# Inverter_Power.net
KiCad netlist of a schematic drawn in Altium Designer
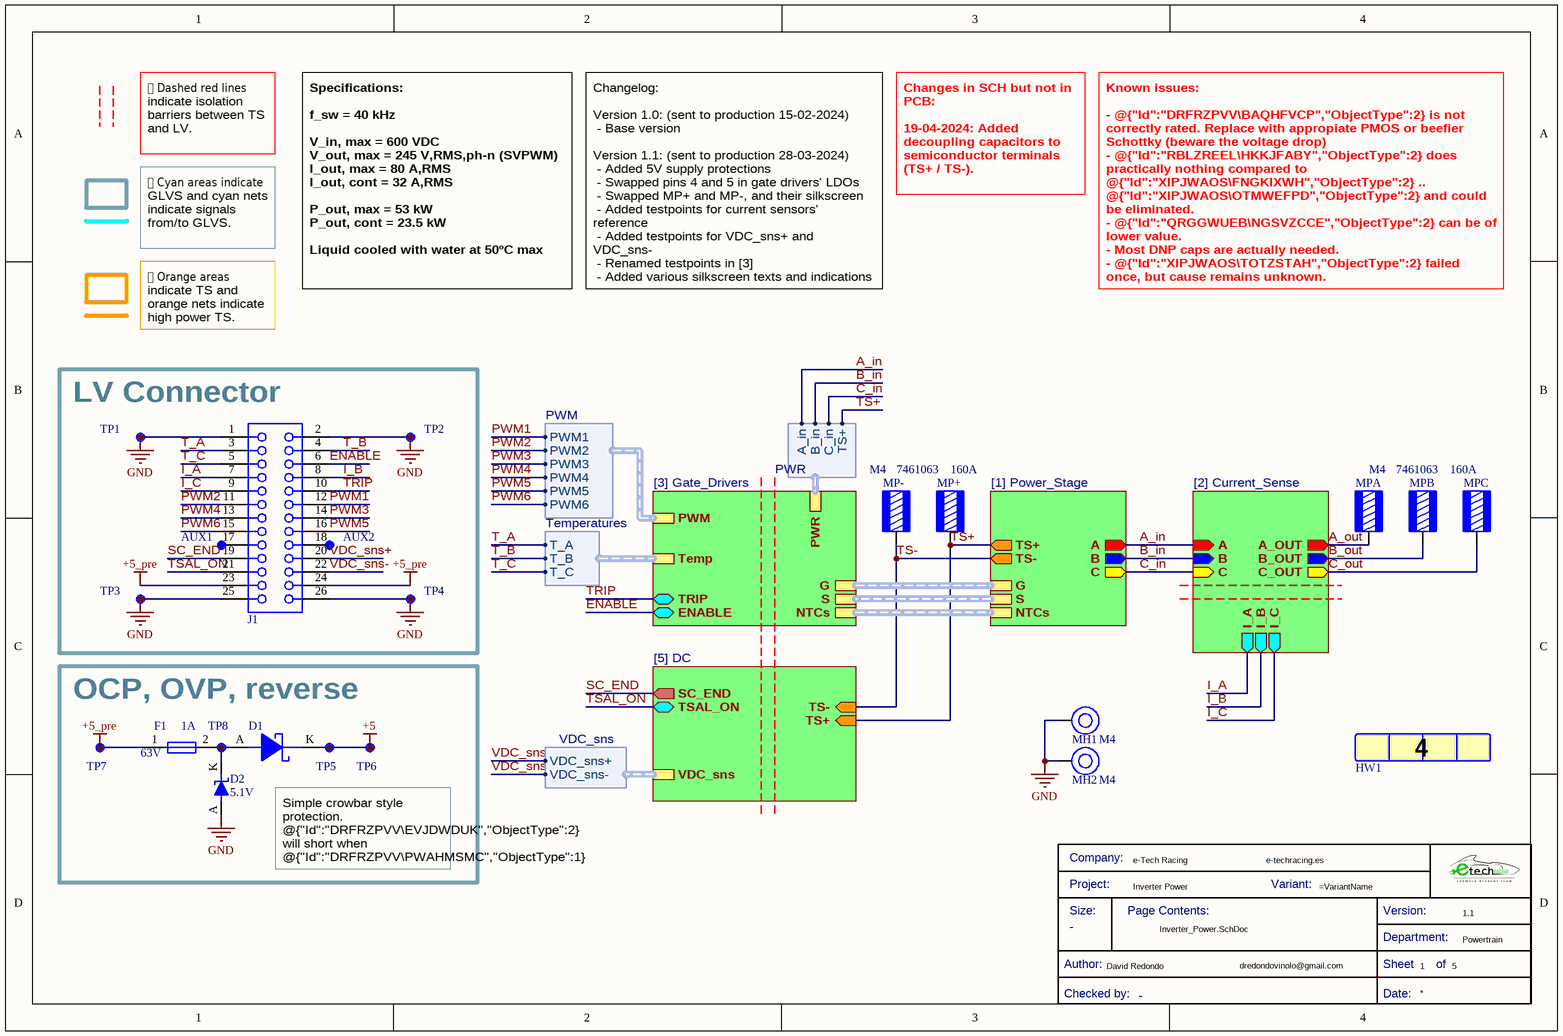
[diagram p0: Inverter_Power.SchDoc]

(export (version "E")
  (design (tool "Eeschema 10.0.6"))
  (components
    (comp (ref "*")
      (value "Title Block_template")
      (description "Standard Title Block")
      (fields
        (field (name "SIZE") "-")
        (field (name ".CREATOR") "GP")
        (field (name ".PCBCHECK") "GP")
        (field (name ".SCHCHECK") "GP")
      )
      (libsource (lib "e-Tech_Racing") (part "Title Block_template"))
    )
    (comp (ref "AUX1")
      (value "TestPoint")
      (footprint "TestPoint")
      (description "Test Point 1x1 mm")
      (fields (field (name ".CREATOR") "GP") (field (name ".PCBCHECK") "GP") (field (name ".SCHCHECK") "GP"))
      (libsource (lib "Inverter_Libraries") (part "TestPoint"))
    )
    (comp (ref "AUX2")
      (value "TestPoint")
      (footprint "TestPoint")
      (description "Test Point 1x1 mm")
      (fields (field (name ".CREATOR") "GP") (field (name ".PCBCHECK") "GP") (field (name ".SCHCHECK") "GP"))
      (libsource (lib "Inverter_Libraries") (part "TestPoint"))
    )
    (comp (ref "D1")
      (value "MBR0530")
      (footprint "DSC-SOD123")
      (description "VR=30V IF=500mA 30pF P=410mW")
      (fields (field (name ".CREATOR") "GP"))
      (libsource (lib "Filter components") (part "DSC-0.5/30-SOD123"))
    )
    (comp (ref "D2")
      (value "BZG05C5V1-E3-TR")
      (footprint "DZ-6.2V-DO-214AC")
      (description "Zener Diode, 5.1V V(Z), 5.88%, 1.25W, Silicon, Unidirectional, DO-214AC")
      (fields
        (field (name "MANUFACTURER") "Vishay")
        (field (name "MANUFACTURER PART NUMBER") "BZG05C5V1-M3-08")
        (field (name "REFERENCE VOLTAGE-NOM") "5.1V")
      )
      (libsource (lib "Inverter_Libraries") (part "DZ-5.1V-DO-214AC"))
    )
    (comp (ref "F1")
      (value "0437001.WRA")
      (footprint "Fuse_1206")
      (description "Fuse Chip Fast Acting 1A 63V SMD Solder Pad 1206 Ceramic T/R Automotive")
      (fields
        (field (name "MANUFACTURER") "Littelfuse")
        (field (name "CURRENT RATING") "1A")
        (field (name "VOLTAGE RATING (DC)") "63V")
        (field (name ".CREATOR") "DO")
      )
      (libsource (lib "Filter components") (part "Fuse_1A_63V_1206"))
    )
    (comp (ref "HW1")
      (value "LOGO CAPAS (4)")
      (footprint "LOGO_LAYERS_4")
      (description "Logo 4 capas")
      (fields (field (name "AUTHOR") "Enric") (field (name "CHECKED") "False"))
      (libsource (lib "Inverter_Libraries") (part "LOGO CAPAS"))
    )
    (comp (ref "J1")
      (value "613026243121")
      (footprint "613026243121")
      (description "WR-PHD Socket Header, THT, Angled, pitch 2.54mm, 2 Row, 26P")
      (fields (field (name "MANUFACTURER") "Wurth Elektronik"))
      (libsource (lib "Inverter_Libraries") (part "613026243121"))
    )
    (comp (ref "MH1")
      (value "Mounting_Hole_M4")
      (footprint "Mounting_Hole_M4")
      (libsource (lib "Electromechanical") (part "Mounting_Hole_M4"))
    )
    (comp (ref "MH2")
      (value "Mounting_Hole_M4")
      (footprint "Mounting_Hole_M4")
      (libsource (lib "Electromechanical") (part "Mounting_Hole_M4"))
    )
    (comp (ref "MP+")
      (value "M4")
      (footprint "7461063_HAL")
      (description "WP-RATR REDCUBE PRESS-FIT right angled, two-rows, L9W9H14mm, M4, 160A")
      (fields
        (field (name "MANUFACTURER PART NUMBER") "7461063")
        (field (name "MANUFACTURER") "Wurth Elektronik")
      )
      (libsource (lib "Inverter_Libraries") (part "7461063"))
    )
    (comp (ref "MP-")
      (value "M4")
      (footprint "7461063_HAL")
      (description "WP-RATR REDCUBE PRESS-FIT right angled, two-rows, L9W9H14mm, M4, 160A")
      (fields
        (field (name "MANUFACTURER PART NUMBER") "7461063")
        (field (name "MANUFACTURER") "Wurth Elektronik")
        (field (name "RATED CURRENT") "160A")
        (field (name "THREAD SIZE") "M4")
      )
      (libsource (lib "Inverter_Libraries") (part "7461063"))
    )
    (comp (ref "MPA")
      (value "M4")
      (footprint "7461063_HAL")
      (description "WP-RATR REDCUBE PRESS-FIT right angled, two-rows, L9W9H14mm, M4, 160A")
      (fields
        (field (name "MANUFACTURER PART NUMBER") "7461063")
        (field (name "MANUFACTURER") "Wurth Elektronik")
      )
      (libsource (lib "Inverter_Libraries") (part "7461063"))
    )
    (comp (ref "MPB")
      (value "M4")
      (footprint "7461063_HAL")
      (description "WP-RATR REDCUBE PRESS-FIT right angled, two-rows, L9W9H14mm, M4, 160A")
      (fields
        (field (name "MANUFACTURER PART NUMBER") "7461063")
        (field (name "MANUFACTURER") "Wurth Elektronik")
        (field (name "RATED CURRENT") "160A")
        (field (name "THREAD SIZE") "M4")
      )
      (libsource (lib "Inverter_Libraries") (part "7461063"))
    )
    (comp (ref "MPC")
      (value "M4")
      (footprint "7461063_HAL")
      (description "WP-RATR REDCUBE PRESS-FIT right angled, two-rows, L9W9H14mm, M4, 160A")
      (fields
        (field (name "MANUFACTURER PART NUMBER") "7461063")
        (field (name "MANUFACTURER") "Wurth Elektronik")
      )
      (libsource (lib "Inverter_Libraries") (part "7461063"))
    )
    (comp (ref "TP1")
      (value "TestPoint")
      (footprint "TestPoint")
      (description "Test Point 1x1 mm")
      (fields (field (name ".CREATOR") "GP") (field (name ".PCBCHECK") "GP") (field (name ".SCHCHECK") "GP"))
      (libsource (lib "Inverter_Libraries") (part "TestPoint"))
    )
    (comp (ref "TP2")
      (value "TestPoint")
      (footprint "TestPoint")
      (description "Test Point 1x1 mm")
      (fields (field (name ".CREATOR") "GP") (field (name ".PCBCHECK") "GP") (field (name ".SCHCHECK") "GP"))
      (libsource (lib "Inverter_Libraries") (part "TestPoint"))
    )
    (comp (ref "TP3")
      (value "TestPoint")
      (footprint "TestPoint")
      (description "Test Point 1x1 mm")
      (fields (field (name ".CREATOR") "GP") (field (name ".PCBCHECK") "GP") (field (name ".SCHCHECK") "GP"))
      (libsource (lib "Inverter_Libraries") (part "TestPoint"))
    )
    (comp (ref "TP4")
      (value "TestPoint")
      (footprint "TestPoint")
      (description "Test Point 1x1 mm")
      (fields (field (name ".CREATOR") "GP") (field (name ".PCBCHECK") "GP") (field (name ".SCHCHECK") "GP"))
      (libsource (lib "Inverter_Libraries") (part "TestPoint"))
    )
    (comp (ref "TP5")
      (value "TestPoint")
      (footprint "TestPoint")
      (description "Test Point 1x1 mm")
      (fields (field (name ".CREATOR") "GP") (field (name ".PCBCHECK") "GP") (field (name ".SCHCHECK") "GP"))
      (libsource (lib "Inverter_Libraries") (part "TestPoint"))
    )
    (comp (ref "TP6")
      (value "TestPoint")
      (footprint "TestPoint")
      (description "Test Point 1x1 mm")
      (fields (field (name ".CREATOR") "GP") (field (name ".PCBCHECK") "GP") (field (name ".SCHCHECK") "GP"))
      (libsource (lib "Inverter_Libraries") (part "TestPoint"))
    )
    (comp (ref "TP7")
      (value "TestPoint")
      (footprint "TestPoint")
      (description "Test Point 1x1 mm")
      (fields (field (name ".CREATOR") "GP") (field (name ".PCBCHECK") "GP") (field (name ".SCHCHECK") "GP"))
      (libsource (lib "Inverter_Libraries") (part "TestPoint"))
    )
    (comp (ref "TP8")
      (value "TestPoint")
      (footprint "TestPoint")
      (description "Test Point 1x1 mm")
      (fields (field (name ".CREATOR") "GP") (field (name ".PCBCHECK") "GP") (field (name ".SCHCHECK") "GP"))
      (libsource (lib "Inverter_Libraries") (part "TestPoint"))
    )
  )
  (nets
    (net (code "5") (name "+5") (class "Default")
      (node (ref "D1") (pin "K") (pinfunction "K_K") (pintype "passive"))
      (node (ref "TP5") (pin "1") (pinfunction "TP_1") (pintype "passive"))
      (node (ref "TP6") (pin "1") (pinfunction "TP_1") (pintype "passive"))
    )
    (net (code "6") (name "+5_pre") (class "Default")
      (node (ref "F1") (pin "1") (pinfunction "1_1") (pintype "passive"))
      (node (ref "J1") (pin "23") (pinfunction "23_23") (pintype "passive"))
      (node (ref "J1") (pin "24") (pinfunction "24_24") (pintype "passive"))
      (node (ref "TP7") (pin "1") (pinfunction "TP_1") (pintype "passive"))
    )
    (net (code "8") (name "/A_out") (class "Default")
      (node (ref "MPA") (pin "1") (pinfunction "1_1") (pintype "passive"))
    )
    (net (code "10") (name "/B_out") (class "Default")
      (node (ref "MPB") (pin "1") (pinfunction "1_1") (pintype "passive"))
    )
    (net (code "11") (name "/C_in") (class "Default")
      (node (ref "MP+") (pin "1") (pinfunction "1_1") (pintype "passive"))
    )
    (net (code "12") (name "/C_out") (class "Default")
      (node (ref "MPC") (pin "1") (pinfunction "1_1") (pintype "passive"))
    )
    (net (code "13") (name "/ENABLE") (class "Default")
      (node (ref "J1") (pin "6") (pinfunction "6_6") (pintype "passive"))
    )
    (net (code "15") (name "/I_A") (class "Default")
      (node (ref "J1") (pin "7") (pinfunction "7_7") (pintype "passive"))
    )
    (net (code "16") (name "/I_B") (class "Default")
      (node (ref "J1") (pin "8") (pinfunction "8_8") (pintype "passive"))
    )
    (net (code "17") (name "/I_C") (class "Default")
      (node (ref "J1") (pin "9") (pinfunction "9_9") (pintype "passive"))
    )
    (net (code "19") (name "/PWM1") (class "Default")
      (node (ref "J1") (pin "12") (pinfunction "12_12") (pintype "passive"))
    )
    (net (code "20") (name "/PWM2") (class "Default")
      (node (ref "J1") (pin "11") (pinfunction "11_11") (pintype "passive"))
    )
    (net (code "21") (name "/PWM3") (class "Default")
      (node (ref "J1") (pin "14") (pinfunction "14_14") (pintype "passive"))
    )
    (net (code "22") (name "/PWM4") (class "Default")
      (node (ref "J1") (pin "13") (pinfunction "13_13") (pintype "passive"))
    )
    (net (code "23") (name "/PWM5") (class "Default")
      (node (ref "J1") (pin "16") (pinfunction "16_16") (pintype "passive"))
    )
    (net (code "24") (name "/PWM6") (class "Default")
      (node (ref "J1") (pin "15") (pinfunction "15_15") (pintype "passive"))
    )
    (net (code "25") (name "/SC_END") (class "Default")
      (node (ref "J1") (pin "19") (pinfunction "19_19") (pintype "passive"))
    )
    (net (code "27") (name "/TRIP") (class "Default")
      (node (ref "J1") (pin "10") (pinfunction "10_10") (pintype "passive"))
    )
    (net (code "28") (name "/TS-") (class "Default")
      (node (ref "MP-") (pin "1") (pinfunction "1_1") (pintype "passive"))
    )
    (net (code "29") (name "/TSAL_ON") (class "Default")
      (node (ref "J1") (pin "21") (pinfunction "21_21") (pintype "passive"))
    )
    (net (code "30") (name "/T_A") (class "Default")
      (node (ref "J1") (pin "3") (pinfunction "3_3") (pintype "passive"))
    )
    (net (code "31") (name "/T_B") (class "Default")
      (node (ref "J1") (pin "4") (pinfunction "4_4") (pintype "passive"))
    )
    (net (code "32") (name "/T_C") (class "Default")
      (node (ref "J1") (pin "5") (pinfunction "5_5") (pintype "passive"))
    )
    (net (code "33") (name "/VDC_sns+") (class "Default")
      (node (ref "J1") (pin "20") (pinfunction "20_20") (pintype "passive"))
    )
    (net (code "34") (name "/VDC_sns-") (class "Default")
      (node (ref "J1") (pin "22") (pinfunction "22_22") (pintype "passive"))
    )
    (net (code "39") (name "GND") (class "Default")
      (node (ref "D2") (pin "A") (pinfunction "A_A") (pintype "passive"))
      (node (ref "J1") (pin "1") (pinfunction "1_1") (pintype "passive"))
      (node (ref "J1") (pin "2") (pinfunction "2_2") (pintype "passive"))
      (node (ref "J1") (pin "25") (pinfunction "25_25") (pintype "passive"))
      (node (ref "J1") (pin "26") (pinfunction "26_26") (pintype "passive"))
      (node (ref "MH1") (pin "1") (pinfunction "1_1") (pintype "passive"))
      (node (ref "MH2") (pin "1") (pinfunction "1_1") (pintype "passive"))
      (node (ref "TP1") (pin "1") (pinfunction "TP_1") (pintype "passive"))
      (node (ref "TP2") (pin "1") (pinfunction "TP_1") (pintype "passive"))
      (node (ref "TP3") (pin "1") (pinfunction "TP_1") (pintype "passive"))
      (node (ref "TP4") (pin "1") (pinfunction "TP_1") (pintype "passive"))
    )
    (net (code "40") (name "Net-(AUX1-TP)") (class "Default")
      (node (ref "AUX1") (pin "1") (pinfunction "TP_1") (pintype "passive"))
      (node (ref "J1") (pin "17") (pinfunction "17_17") (pintype "passive"))
    )
    (net (code "41") (name "Net-(AUX2-TP)") (class "Default")
      (node (ref "AUX2") (pin "1") (pinfunction "TP_1") (pintype "passive"))
      (node (ref "J1") (pin "18") (pinfunction "18_18") (pintype "passive"))
    )
    (net (code "42") (name "Net-(TP8-TP)") (class "Default")
      (node (ref "D1") (pin "A") (pinfunction "A_A") (pintype "passive"))
      (node (ref "D2") (pin "K") (pinfunction "K_K") (pintype "passive"))
      (node (ref "F1") (pin "2") (pinfunction "2_2") (pintype "passive"))
      (node (ref "TP8") (pin "1") (pinfunction "TP_1") (pintype "passive"))
    )
  )
)
